# UberHidBoard1.net
KiCad netlist of a schematic drawn in EAGLE
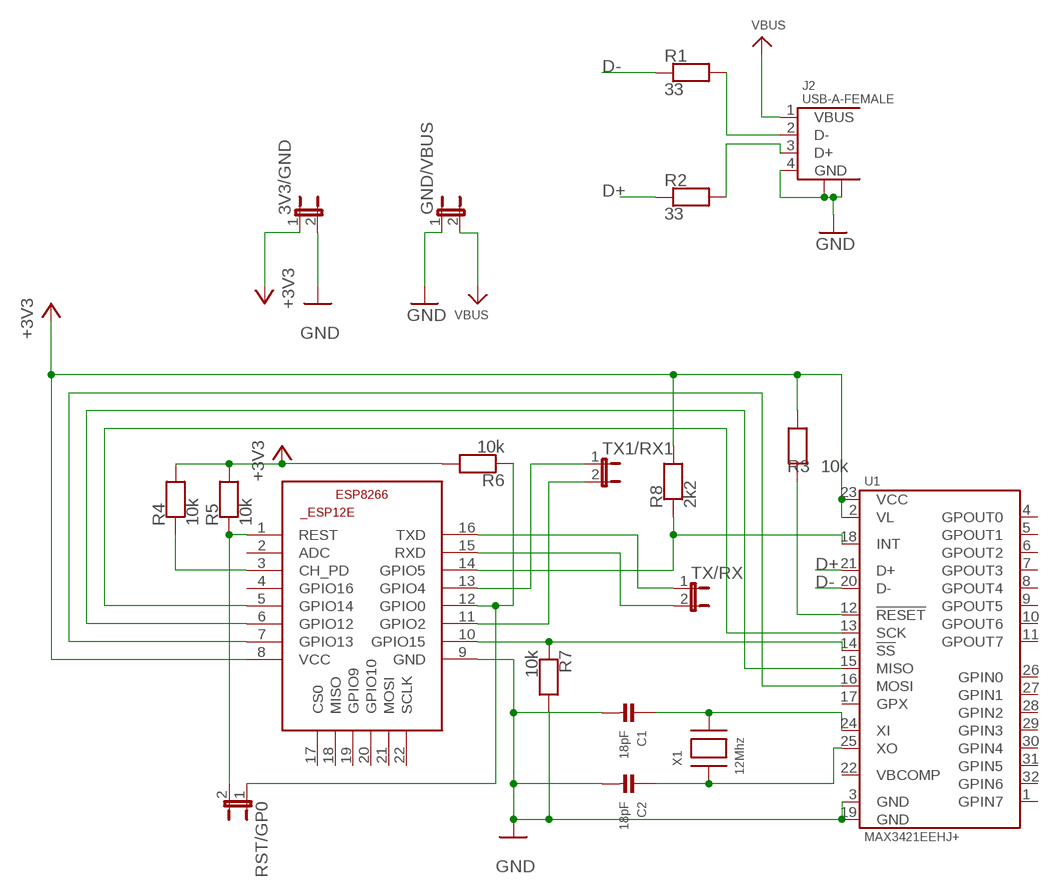
[diagram p0: schematic, sheet 1]

(export (version "E")
  (design (tool "Eeschema 10.0.6"))
  (components
    (comp (ref "3V3/GND")
      (value "JUMPER2")
      (footprint "eagle-import:JUMPER2")
      (libsource (lib "eagle-import") (part "JUMPER2"))
    )
    (comp (ref "C1")
      (value "18pF")
      (footprint "eagle-import:0805")
      (libsource (lib "eagle-import") (part "CAP_CERAMIC0805"))
    )
    (comp (ref "C2")
      (value "18pF")
      (footprint "eagle-import:0805")
      (libsource (lib "eagle-import") (part "CAP_CERAMIC0805"))
    )
    (comp (ref "ESP8266")
      (value "ESP8266-12EESP12E")
      (footprint "eagle-import:ESP8266-ESP12E")
      (libsource (lib "eagle-import") (part "ESP8266-12EESP12E"))
    )
    (comp (ref "GND/VBUS")
      (value "JUMPER2")
      (footprint "eagle-import:JUMPER2")
      (libsource (lib "eagle-import") (part "JUMPER2"))
    )
    (comp (ref "J2")
      (value "USB-A-FEMALE")
      (footprint "eagle-import:USB-A-FEMALE")
      (libsource (lib "eagle-import") (part "USB-A-FEMALE"))
    )
    (comp (ref "R1")
      (value "33")
      (footprint "eagle-import:0805")
      (libsource (lib "eagle-import") (part "RESISTOR0805"))
    )
    (comp (ref "R2")
      (value "33")
      (footprint "eagle-import:0805")
      (libsource (lib "eagle-import") (part "RESISTOR0805"))
    )
    (comp (ref "R3")
      (value "10k")
      (footprint "eagle-import:0805")
      (libsource (lib "eagle-import") (part "RESISTOR0805"))
    )
    (comp (ref "R4")
      (value "10k")
      (footprint "eagle-import:0805")
      (libsource (lib "eagle-import") (part "RESISTOR0805"))
    )
    (comp (ref "R5")
      (value "10k")
      (footprint "eagle-import:0805")
      (libsource (lib "eagle-import") (part "RESISTOR0805"))
    )
    (comp (ref "R6")
      (value "10k")
      (footprint "eagle-import:0805")
      (libsource (lib "eagle-import") (part "RESISTOR0805"))
    )
    (comp (ref "R7")
      (value "10k")
      (footprint "eagle-import:0805")
      (libsource (lib "eagle-import") (part "RESISTOR0805"))
    )
    (comp (ref "R8")
      (value "2k2")
      (footprint "eagle-import:0805")
      (libsource (lib "eagle-import") (part "RESISTOR0805"))
    )
    (comp (ref "RST/GP0")
      (value "JUMPER2")
      (footprint "eagle-import:JUMPER2")
      (libsource (lib "eagle-import") (part "JUMPER2"))
    )
    (comp (ref "TX/RX")
      (value "JUMPER2")
      (footprint "eagle-import:JUMPER2")
      (libsource (lib "eagle-import") (part "JUMPER2"))
    )
    (comp (ref "TX1/RX1")
      (value "JUMPER2")
      (footprint "eagle-import:JUMPER2")
      (libsource (lib "eagle-import") (part "JUMPER2"))
    )
    (comp (ref "U1")
      (value "MAX3421EEHJ+")
      (footprint "eagle-import:LQFP-23")
      (libsource (lib "eagle-import") (part "MAX3421EEHJ+"))
    )
    (comp (ref "X1")
      (value "12Mhz")
      (footprint "eagle-import:XTAL3215")
      (libsource (lib "eagle-import") (part "XTAL-3.2X1.5"))
    )
  )
  (nets
    (net (code "1") (name "+3V3") (class "Default")
      (node (ref "3V3/GND") (pin "1") (pinfunction "1_1") (pintype "passive"))
      (node (ref "ESP8266") (pin "8") (pinfunction "VCC_8") (pintype "bidirectional"))
      (node (ref "R3") (pin "2") (pinfunction "2_2") (pintype "passive"))
      (node (ref "R4") (pin "2") (pinfunction "2_2") (pintype "passive"))
      (node (ref "R5") (pin "2") (pinfunction "2_2") (pintype "passive"))
      (node (ref "R6") (pin "2") (pinfunction "2_2") (pintype "passive"))
      (node (ref "R8") (pin "2") (pinfunction "2_2") (pintype "passive"))
      (node (ref "U1") (pin "2") (pinfunction "VL_2") (pintype "bidirectional"))
      (node (ref "U1") (pin "23") (pinfunction "VCC_23") (pintype "bidirectional"))
    )
    (net (code "2") (name "/D+") (class "Default")
      (node (ref "R2") (pin "1") (pinfunction "1_1") (pintype "passive"))
      (node (ref "U1") (pin "21") (pinfunction "D+_21") (pintype "bidirectional"))
    )
    (net (code "3") (name "/D-") (class "Default")
      (node (ref "R1") (pin "1") (pinfunction "1_1") (pintype "passive"))
      (node (ref "U1") (pin "20") (pinfunction "D-_20") (pintype "bidirectional"))
    )
    (net (code "4") (name "GND") (class "Default")
      (node (ref "3V3/GND") (pin "2") (pinfunction "2_2") (pintype "passive"))
      (node (ref "C1") (pin "2") (pinfunction "P$2_2") (pintype "passive"))
      (node (ref "C2") (pin "2") (pinfunction "P$2_2") (pintype "passive"))
      (node (ref "ESP8266") (pin "9") (pinfunction "GND_9") (pintype "bidirectional"))
      (node (ref "GND/VBUS") (pin "1") (pinfunction "1_1") (pintype "passive"))
      (node (ref "J2") (pin "4") (pinfunction "GND_4") (pintype "bidirectional"))
      (node (ref "J2") (pin "P$1") (pinfunction "P$1_P$1") (pintype "bidirectional"))
      (node (ref "J2") (pin "P$2") (pinfunction "P$2_P$2") (pintype "bidirectional"))
      (node (ref "R7") (pin "2") (pinfunction "2_2") (pintype "passive"))
      (node (ref "U1") (pin "19") (pinfunction "GND_19") (pintype "bidirectional"))
      (node (ref "U1") (pin "3") (pinfunction "GND_3") (pintype "bidirectional"))
    )
    (net (code "5") (name "Net-(C1-P$1)") (class "Default")
      (node (ref "C1") (pin "1") (pinfunction "P$1_1") (pintype "passive"))
      (node (ref "U1") (pin "24") (pinfunction "XI_24") (pintype "bidirectional"))
      (node (ref "X1") (pin "P$2") (pinfunction "P$2_P$2") (pintype "bidirectional"))
    )
    (net (code "6") (name "Net-(C2-P$1)") (class "Default")
      (node (ref "C2") (pin "1") (pinfunction "P$1_1") (pintype "passive"))
      (node (ref "U1") (pin "25") (pinfunction "XO_25") (pintype "bidirectional"))
      (node (ref "X1") (pin "P$1") (pinfunction "P$1_P$1") (pintype "bidirectional"))
    )
    (net (code "7") (name "Net-(ESP8266-CH_PD)") (class "Default")
      (node (ref "ESP8266") (pin "3") (pinfunction "CH_PD_3") (pintype "bidirectional"))
      (node (ref "R4") (pin "1") (pinfunction "1_1") (pintype "passive"))
    )
    (net (code "8") (name "Net-(ESP8266-GPIO0)") (class "Default")
      (node (ref "ESP8266") (pin "12") (pinfunction "GPIO0_12") (pintype "bidirectional"))
      (node (ref "R6") (pin "1") (pinfunction "1_1") (pintype "passive"))
      (node (ref "RST/GP0") (pin "1") (pinfunction "1_1") (pintype "passive"))
    )
    (net (code "9") (name "Net-(ESP8266-GPIO2)") (class "Default")
      (node (ref "ESP8266") (pin "11") (pinfunction "GPIO2_11") (pintype "bidirectional"))
      (node (ref "TX1/RX1") (pin "2") (pinfunction "2_2") (pintype "passive"))
    )
    (net (code "10") (name "Net-(ESP8266-GPIO4)") (class "Default")
      (node (ref "ESP8266") (pin "13") (pinfunction "GPIO4_13") (pintype "bidirectional"))
      (node (ref "TX1/RX1") (pin "1") (pinfunction "1_1") (pintype "passive"))
    )
    (net (code "11") (name "Net-(ESP8266-GPIO5)") (class "Default")
      (node (ref "ESP8266") (pin "14") (pinfunction "GPIO5_14") (pintype "bidirectional"))
      (node (ref "R8") (pin "1") (pinfunction "1_1") (pintype "passive"))
      (node (ref "U1") (pin "18") (pinfunction "INT_18") (pintype "bidirectional"))
    )
    (net (code "12") (name "Net-(ESP8266-GPIO12)") (class "Default")
      (node (ref "ESP8266") (pin "6") (pinfunction "GPIO12_6") (pintype "bidirectional"))
      (node (ref "U1") (pin "15") (pinfunction "MISO_15") (pintype "bidirectional"))
    )
    (net (code "13") (name "Net-(ESP8266-GPIO13)") (class "Default")
      (node (ref "ESP8266") (pin "7") (pinfunction "GPIO13_7") (pintype "bidirectional"))
      (node (ref "U1") (pin "16") (pinfunction "MOSI_16") (pintype "bidirectional"))
    )
    (net (code "14") (name "Net-(ESP8266-GPIO14)") (class "Default")
      (node (ref "ESP8266") (pin "5") (pinfunction "GPIO14_5") (pintype "bidirectional"))
      (node (ref "U1") (pin "13") (pinfunction "SCK_13") (pintype "bidirectional"))
    )
    (net (code "15") (name "Net-(ESP8266-GPIO15)") (class "Default")
      (node (ref "ESP8266") (pin "10") (pinfunction "GPIO15_10") (pintype "bidirectional"))
      (node (ref "R7") (pin "1") (pinfunction "1_1") (pintype "passive"))
      (node (ref "U1") (pin "14") (pinfunction "~{SS}_14") (pintype "bidirectional"))
    )
    (net (code "16") (name "Net-(ESP8266-REST)") (class "Default")
      (node (ref "ESP8266") (pin "1") (pinfunction "REST_1") (pintype "bidirectional"))
      (node (ref "R5") (pin "1") (pinfunction "1_1") (pintype "passive"))
      (node (ref "RST/GP0") (pin "2") (pinfunction "2_2") (pintype "passive"))
    )
    (net (code "17") (name "Net-(ESP8266-RXD)") (class "Default")
      (node (ref "ESP8266") (pin "15") (pinfunction "RXD_15") (pintype "bidirectional"))
      (node (ref "TX/RX") (pin "2") (pinfunction "2_2") (pintype "passive"))
    )
    (net (code "18") (name "Net-(ESP8266-TXD)") (class "Default")
      (node (ref "ESP8266") (pin "16") (pinfunction "TXD_16") (pintype "bidirectional"))
      (node (ref "TX/RX") (pin "1") (pinfunction "1_1") (pintype "passive"))
    )
    (net (code "19") (name "Net-(J2-D+)") (class "Default")
      (node (ref "J2") (pin "3") (pinfunction "D+_3") (pintype "bidirectional"))
      (node (ref "R2") (pin "2") (pinfunction "2_2") (pintype "passive"))
    )
    (net (code "20") (name "Net-(J2-D-)") (class "Default")
      (node (ref "J2") (pin "2") (pinfunction "D-_2") (pintype "bidirectional"))
      (node (ref "R1") (pin "2") (pinfunction "2_2") (pintype "passive"))
    )
    (net (code "21") (name "Net-(U1-~{RESET})") (class "Default")
      (node (ref "R3") (pin "1") (pinfunction "1_1") (pintype "passive"))
      (node (ref "U1") (pin "12") (pinfunction "~{RESET}_12") (pintype "bidirectional"))
    )
    (net (code "22") (name "VBUS") (class "Default")
      (node (ref "GND/VBUS") (pin "2") (pinfunction "2_2") (pintype "passive"))
      (node (ref "J2") (pin "1") (pinfunction "VBUS_1") (pintype "bidirectional"))
    )
    (net (code "23") (name "unconnected-(ESP8266-ADC-Pad2)") (class "Default")
      (node (ref "ESP8266") (pin "2") (pinfunction "ADC_2") (pintype "bidirectional"))
    )
    (net (code "24") (name "unconnected-(ESP8266-CS0-Pad17)") (class "Default")
      (node (ref "ESP8266") (pin "17") (pinfunction "CS0_17") (pintype "bidirectional"))
    )
    (net (code "25") (name "unconnected-(ESP8266-GPIO9-Pad19)") (class "Default")
      (node (ref "ESP8266") (pin "19") (pinfunction "GPIO9_19") (pintype "bidirectional"))
    )
    (net (code "26") (name "unconnected-(ESP8266-GPIO10-Pad20)") (class "Default")
      (node (ref "ESP8266") (pin "20") (pinfunction "GPIO10_20") (pintype "bidirectional"))
    )
    (net (code "27") (name "unconnected-(ESP8266-GPIO16-Pad4)") (class "Default")
      (node (ref "ESP8266") (pin "4") (pinfunction "GPIO16_4") (pintype "bidirectional"))
    )
    (net (code "28") (name "unconnected-(ESP8266-MISO-Pad18)") (class "Default")
      (node (ref "ESP8266") (pin "18") (pinfunction "MISO_18") (pintype "bidirectional"))
    )
    (net (code "29") (name "unconnected-(ESP8266-MOSI-Pad21)") (class "Default")
      (node (ref "ESP8266") (pin "21") (pinfunction "MOSI_21") (pintype "bidirectional"))
    )
    (net (code "30") (name "unconnected-(ESP8266-SCLK-Pad22)") (class "Default")
      (node (ref "ESP8266") (pin "22") (pinfunction "SCLK_22") (pintype "bidirectional"))
    )
    (net (code "31") (name "unconnected-(U1-GPIN0-Pad26)") (class "Default")
      (node (ref "U1") (pin "26") (pinfunction "GPIN0_26") (pintype "bidirectional"))
    )
    (net (code "32") (name "unconnected-(U1-GPIN1-Pad27)") (class "Default")
      (node (ref "U1") (pin "27") (pinfunction "GPIN1_27") (pintype "bidirectional"))
    )
    (net (code "33") (name "unconnected-(U1-GPIN2-Pad28)") (class "Default")
      (node (ref "U1") (pin "28") (pinfunction "GPIN2_28") (pintype "bidirectional"))
    )
    (net (code "34") (name "unconnected-(U1-GPIN3-Pad29)") (class "Default")
      (node (ref "U1") (pin "29") (pinfunction "GPIN3_29") (pintype "bidirectional"))
    )
    (net (code "35") (name "unconnected-(U1-GPIN4-Pad30)") (class "Default")
      (node (ref "U1") (pin "30") (pinfunction "GPIN4_30") (pintype "bidirectional"))
    )
    (net (code "36") (name "unconnected-(U1-GPIN5-Pad31)") (class "Default")
      (node (ref "U1") (pin "31") (pinfunction "GPIN5_31") (pintype "bidirectional"))
    )
    (net (code "37") (name "unconnected-(U1-GPIN6-Pad32)") (class "Default")
      (node (ref "U1") (pin "32") (pinfunction "GPIN6_32") (pintype "bidirectional"))
    )
    (net (code "38") (name "unconnected-(U1-GPIN7-Pad1)") (class "Default")
      (node (ref "U1") (pin "1") (pinfunction "GPIN7_1") (pintype "bidirectional"))
    )
    (net (code "39") (name "unconnected-(U1-GPOUT0-Pad4)") (class "Default")
      (node (ref "U1") (pin "4") (pinfunction "GPOUT0_4") (pintype "bidirectional"))
    )
    (net (code "40") (name "unconnected-(U1-GPOUT1-Pad5)") (class "Default")
      (node (ref "U1") (pin "5") (pinfunction "GPOUT1_5") (pintype "bidirectional"))
    )
    (net (code "41") (name "unconnected-(U1-GPOUT2-Pad6)") (class "Default")
      (node (ref "U1") (pin "6") (pinfunction "GPOUT2_6") (pintype "bidirectional"))
    )
    (net (code "42") (name "unconnected-(U1-GPOUT3-Pad7)") (class "Default")
      (node (ref "U1") (pin "7") (pinfunction "GPOUT3_7") (pintype "bidirectional"))
    )
    (net (code "43") (name "unconnected-(U1-GPOUT4-Pad8)") (class "Default")
      (node (ref "U1") (pin "8") (pinfunction "GPOUT4_8") (pintype "bidirectional"))
    )
    (net (code "44") (name "unconnected-(U1-GPOUT5-Pad9)") (class "Default")
      (node (ref "U1") (pin "9") (pinfunction "GPOUT5_9") (pintype "bidirectional"))
    )
    (net (code "45") (name "unconnected-(U1-GPOUT6-Pad10)") (class "Default")
      (node (ref "U1") (pin "10") (pinfunction "GPOUT6_10") (pintype "bidirectional"))
    )
    (net (code "46") (name "unconnected-(U1-GPOUT7-Pad11)") (class "Default")
      (node (ref "U1") (pin "11") (pinfunction "GPOUT7_11") (pintype "bidirectional"))
    )
    (net (code "47") (name "unconnected-(U1-GPX-Pad17)") (class "Default")
      (node (ref "U1") (pin "17") (pinfunction "GPX_17") (pintype "bidirectional"))
    )
    (net (code "48") (name "unconnected-(U1-VBCOMP-Pad22)") (class "Default")
      (node (ref "U1") (pin "22") (pinfunction "VBCOMP_22") (pintype "bidirectional"))
    )
  )
)
